# Magnetometer.net
KiCad netlist of a schematic drawn in EAGLE
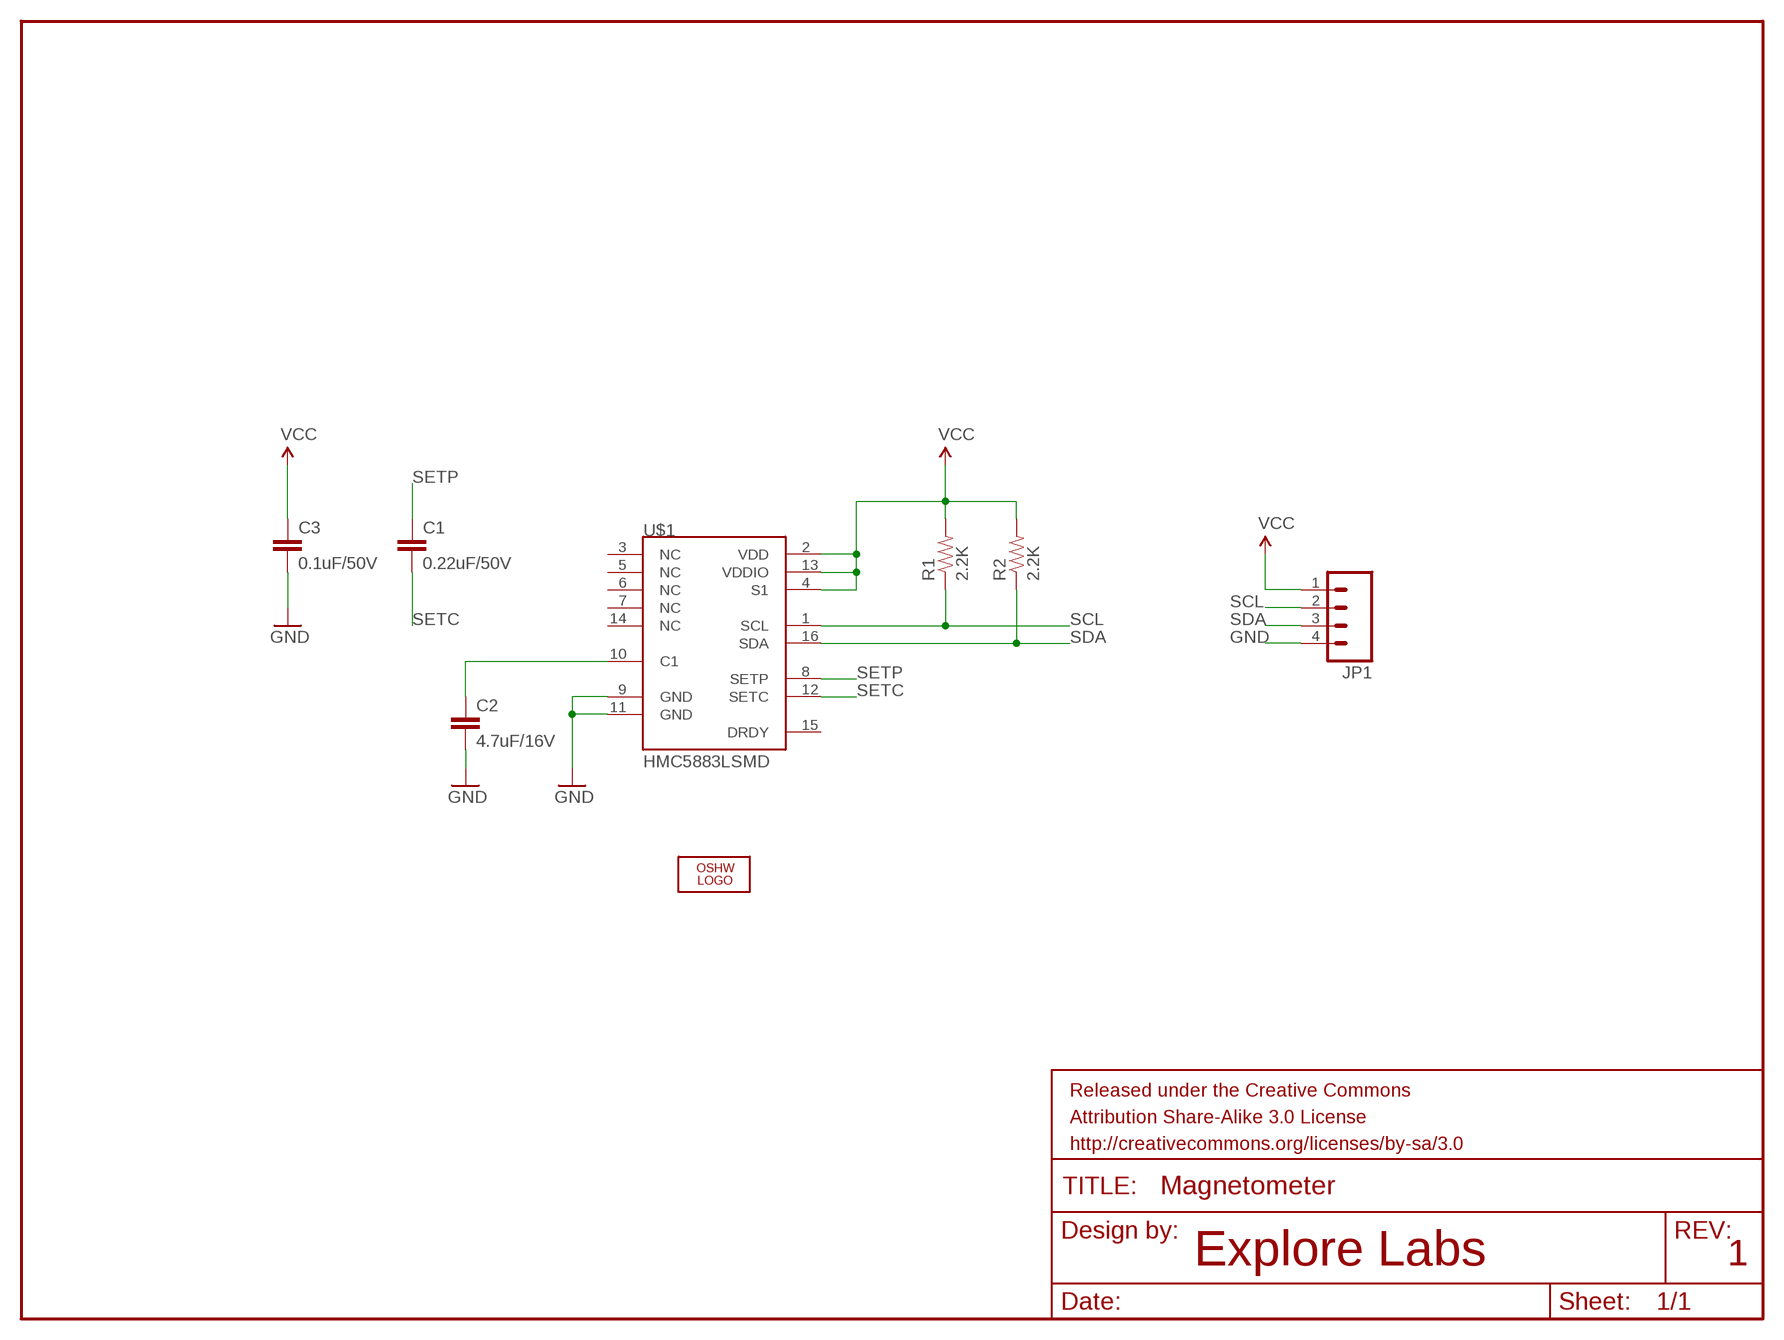
[diagram p0: schematic, sheet 1]

(export (version "E")
  (design (tool "Eeschema 10.0.6"))
  (components
    (comp (ref "C1")
      (value "0.22uF/50V")
      (footprint "eagle-import:1206")
      (libsource (lib "eagle-import") (part "CAP1206"))
    )
    (comp (ref "C2")
      (value "4.7uF/16V")
      (footprint "eagle-import:1206")
      (libsource (lib "eagle-import") (part "CAP1206"))
    )
    (comp (ref "C3")
      (value "0.1uF/50V")
      (footprint "eagle-import:0805")
      (libsource (lib "eagle-import") (part "CAP0805"))
    )
    (comp (ref "JP1")
      (value "M04PTH")
      (footprint "eagle-import:1X04")
      (libsource (lib "eagle-import") (part "M04PTH"))
    )
    (comp (ref "LOGO1")
      (value "OSHW_LOGO_FILLX0100-NT")
      (footprint "eagle-import:OSHW_FILLX100_NOTEXT")
      (libsource (lib "eagle-import") (part "OSHW_LOGO_FILLX0100-NT"))
    )
    (comp (ref "R1")
      (value "2.2K")
      (footprint "eagle-import:0603-RES")
      (libsource (lib "eagle-import") (part "RESISTOR0603-RES"))
    )
    (comp (ref "R2")
      (value "2.2K")
      (footprint "eagle-import:0603-RES")
      (libsource (lib "eagle-import") (part "RESISTOR0603-RES"))
    )
    (comp (ref "U$1")
      (value "HMC5883LSMD")
      (footprint "eagle-import:16LPCC")
      (libsource (lib "eagle-import") (part "HMC5883LSMD"))
    )
  )
  (nets
    (net (code "1") (name "/SCL") (class "Default")
      (node (ref "JP1") (pin "2") (pinfunction "2_2") (pintype "passive"))
      (node (ref "R1") (pin "1") (pinfunction "1_1") (pintype "passive"))
      (node (ref "U$1") (pin "1") (pinfunction "SCL_1") (pintype "bidirectional"))
    )
    (net (code "2") (name "/SDA") (class "Default")
      (node (ref "JP1") (pin "3") (pinfunction "3_3") (pintype "passive"))
      (node (ref "R2") (pin "1") (pinfunction "1_1") (pintype "passive"))
      (node (ref "U$1") (pin "16") (pinfunction "SDA_16") (pintype "bidirectional"))
    )
    (net (code "3") (name "/SETC") (class "Default")
      (node (ref "C1") (pin "2") (pinfunction "2_2") (pintype "passive"))
      (node (ref "U$1") (pin "12") (pinfunction "SETC_12") (pintype "bidirectional"))
    )
    (net (code "4") (name "/SETP") (class "Default")
      (node (ref "C1") (pin "1") (pinfunction "1_1") (pintype "passive"))
      (node (ref "U$1") (pin "8") (pinfunction "SETP_8") (pintype "bidirectional"))
    )
    (net (code "5") (name "GND") (class "Default")
      (node (ref "C2") (pin "2") (pinfunction "2_2") (pintype "passive"))
      (node (ref "C3") (pin "2") (pinfunction "2_2") (pintype "passive"))
      (node (ref "JP1") (pin "4") (pinfunction "4_4") (pintype "passive"))
      (node (ref "U$1") (pin "11") (pinfunction "GND_11") (pintype "bidirectional"))
      (node (ref "U$1") (pin "9") (pinfunction "GND_9") (pintype "bidirectional"))
    )
    (net (code "6") (name "Net-(U$1-C1)") (class "Default")
      (node (ref "C2") (pin "1") (pinfunction "1_1") (pintype "passive"))
      (node (ref "U$1") (pin "10") (pinfunction "C1_10") (pintype "bidirectional"))
    )
    (net (code "7") (name "VCC") (class "Default")
      (node (ref "C3") (pin "1") (pinfunction "1_1") (pintype "passive"))
      (node (ref "JP1") (pin "1") (pinfunction "1_1") (pintype "passive"))
      (node (ref "R1") (pin "2") (pinfunction "2_2") (pintype "passive"))
      (node (ref "R2") (pin "2") (pinfunction "2_2") (pintype "passive"))
      (node (ref "U$1") (pin "13") (pinfunction "VDDIO_13") (pintype "bidirectional"))
      (node (ref "U$1") (pin "2") (pinfunction "VDD_2") (pintype "bidirectional"))
      (node (ref "U$1") (pin "4") (pinfunction "S1_4") (pintype "bidirectional"))
    )
    (net (code "8") (name "unconnected-(U$1-DRDY-Pad15)") (class "Default")
      (node (ref "U$1") (pin "15") (pinfunction "DRDY_15") (pintype "bidirectional"))
    )
    (net (code "9") (name "unconnected-(U$1-NC-Pad3)") (class "Default")
      (node (ref "U$1") (pin "3") (pinfunction "NC_3") (pintype "bidirectional"))
    )
    (net (code "10") (name "unconnected-(U$1-NC-Pad5)") (class "Default")
      (node (ref "U$1") (pin "5") (pinfunction "NC_5") (pintype "bidirectional"))
    )
    (net (code "11") (name "unconnected-(U$1-NC-Pad6)") (class "Default")
      (node (ref "U$1") (pin "6") (pinfunction "NC_6") (pintype "bidirectional"))
    )
    (net (code "12") (name "unconnected-(U$1-NC-Pad7)") (class "Default")
      (node (ref "U$1") (pin "7") (pinfunction "NC_7") (pintype "bidirectional"))
    )
    (net (code "13") (name "unconnected-(U$1-NC-Pad14)") (class "Default")
      (node (ref "U$1") (pin "14") (pinfunction "NC_14") (pintype "bidirectional"))
    )
  )
)
